# Power_Distribution_-_Spares.net
KiCad netlist of a schematic drawn in Altium Designer
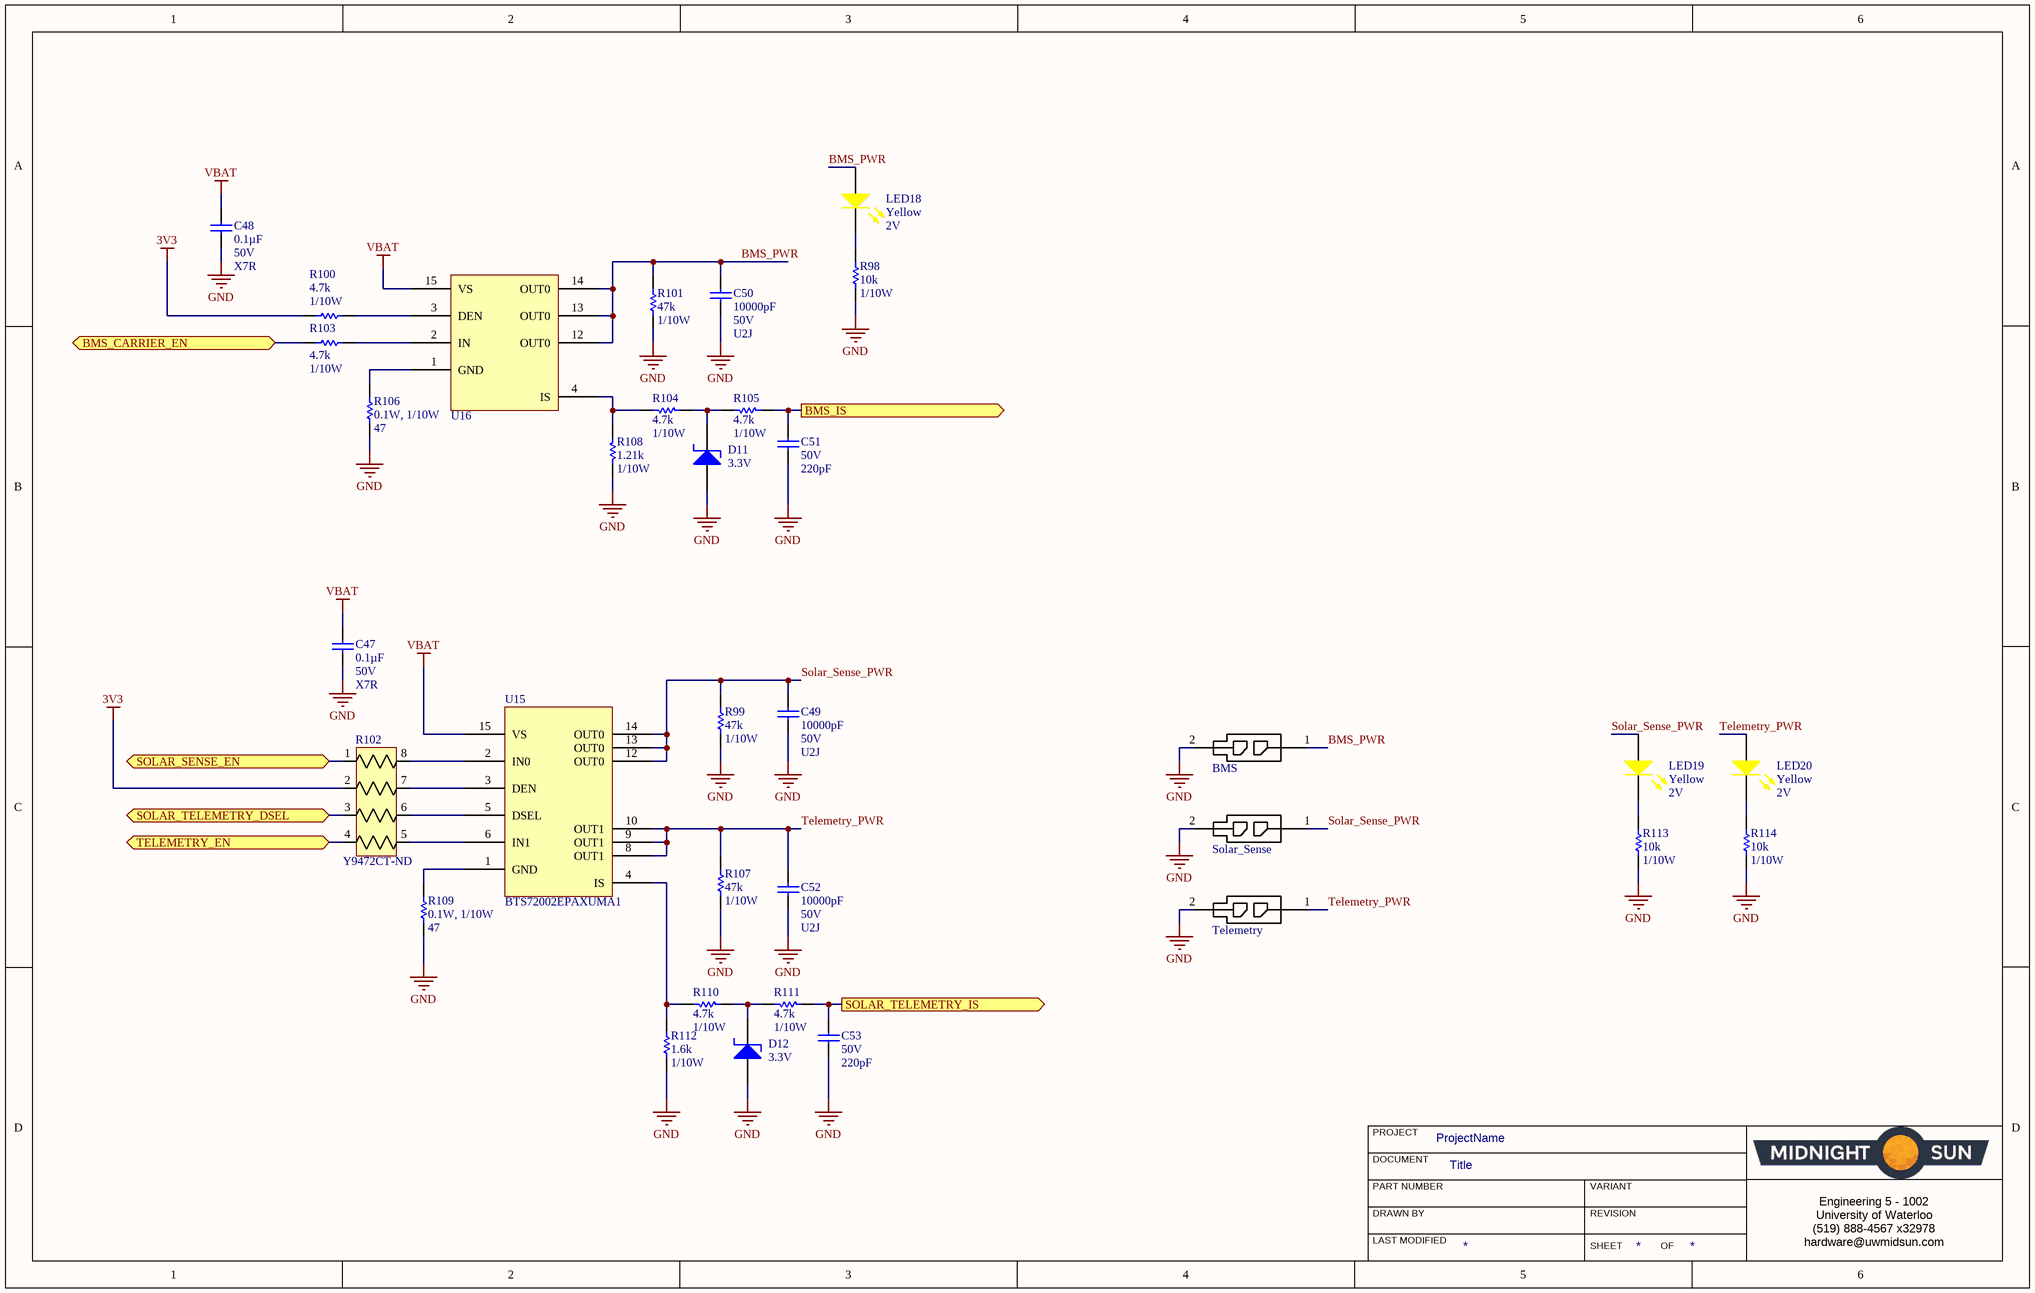
[diagram p0: Power Distribution - Spares.SchDoc]

(export (version "E")
  (design (tool "Eeschema 10.0.6"))
  (components
    (comp (ref "BMS")
      (value "CONN 2POS MICRO-FIT 3mm")
      (footprint "CONN, 2POS MICRO-FIT")
      (description "Connector Header Through Hole 2 position")
      (fields (field (name "MANUFACTURER") "Molex") (field (name "MANUFACTURER PART NUMBER") "43045-0227"))
      (libsource (lib "Schematic Diagrams") (part "CONN 2POS MICRO-FIT 3mm"))
    )
    (comp (ref "C47")
      (value "CAP CER 0.1UF 50V 10% X7R 0603")
      (footprint "CAP, 0603")
      (description "0.10µF ±10% 50V Ceramic Capacitor X7R 0603 (1608 Metric)")
      (fields
        (field (name "TOLERANCE") "±10%")
        (field (name "CAPACITANCE") "0.1µF")
        (field (name "VOLTAGE") "50V")
        (field (name "TEMPERATURE COEFFICIENT") "X7R")
      )
      (libsource (lib "Schematic Diagrams") (part "CAP CER 0.1UF 50V 10% X7R 0603"))
    )
    (comp (ref "C48")
      (value "CAP CER 0.1UF 50V 10% X7R 0603")
      (footprint "CAP, 0603")
      (description "0.10µF ±10% 50V Ceramic Capacitor X7R 0603 (1608 Metric)")
      (fields
        (field (name "TOLERANCE") "±10%")
        (field (name "CAPACITANCE") "0.1µF")
        (field (name "VOLTAGE") "50V")
        (field (name "TEMPERATURE COEFFICIENT") "X7R")
      )
      (libsource (lib "Schematic Diagrams") (part "CAP CER 0.1UF 50V 10% X7R 0603"))
    )
    (comp (ref "C49")
      (value "CAP CER 10nF 50V 5% X7R 0603")
      (footprint "CAP, 0603")
      (description "10000pF ±5% 50V Ceramic Capacitor U2J 0603 (1608 Metric)")
      (fields
        (field (name "TOLERANCE") "±5%")
        (field (name "CAPACITANCE") "10000pF")
        (field (name "VOLTAGE") "50V")
        (field (name "TEMPERATURE COEFFICIENT") "U2J")
      )
      (libsource (lib "Schematic Diagrams") (part "CAP CER 10nF 50V 5% X7R 0603"))
    )
    (comp (ref "C50")
      (value "CAP CER 10nF 50V 5% X7R 0603")
      (footprint "CAP, 0603")
      (description "10000pF ±5% 50V Ceramic Capacitor U2J 0603 (1608 Metric)")
      (fields
        (field (name "TOLERANCE") "±5%")
        (field (name "CAPACITANCE") "10000pF")
        (field (name "VOLTAGE") "50V")
        (field (name "TEMPERATURE COEFFICIENT") "U2J")
      )
      (libsource (lib "Schematic Diagrams") (part "CAP CER 10nF 50V 5% X7R 0603"))
    )
    (comp (ref "C51")
      (value "CAP CER 220PF 50V C0G/NP0 0603")
      (footprint "CAP, 0603")
      (description "220pF ±5% 50V Ceramic Capacitor C0G, NP0 0603 (1608 Metric)")
      (fields
        (field (name "MANUFACTURER") "KEMET")
        (field (name "TOLERANCE") "5%")
        (field (name "VOLTAGE RATING") "50V")
        (field (name "CAPACITANCE") "220pF")
      )
      (libsource (lib "Schematic Diagrams") (part "CAP CER 220PF 50V C0G/NP0 0603"))
    )
    (comp (ref "C52")
      (value "CAP CER 10nF 50V 5% X7R 0603")
      (footprint "CAP, 0603")
      (description "10000pF ±5% 50V Ceramic Capacitor U2J 0603 (1608 Metric)")
      (fields
        (field (name "TOLERANCE") "±5%")
        (field (name "CAPACITANCE") "10000pF")
        (field (name "VOLTAGE") "50V")
        (field (name "TEMPERATURE COEFFICIENT") "U2J")
      )
      (libsource (lib "Schematic Diagrams") (part "CAP CER 10nF 50V 5% X7R 0603"))
    )
    (comp (ref "C53")
      (value "CAP CER 220PF 50V C0G/NP0 0603")
      (footprint "CAP, 0603")
      (description "220pF ±5% 50V Ceramic Capacitor C0G, NP0 0603 (1608 Metric)")
      (fields
        (field (name "MANUFACTURER") "KEMET")
        (field (name "TOLERANCE") "5%")
        (field (name "VOLTAGE RATING") "50V")
        (field (name "CAPACITANCE") "220pF")
      )
      (libsource (lib "Schematic Diagrams") (part "CAP CER 220PF 50V C0G/NP0 0603"))
    )
    (comp (ref "D11")
      (value "DIODE ZENER 3.3V 200MW SOD323")
      (footprint "sod-323")
      (description "Zener Diode 3.3V 200mW ±5% Surface Mount SOD-323")
      (fields (field (name "VOLTAGE") "3.3V"))
      (libsource (lib "Schematic Diagrams") (part "DIODE ZENER 3.3V 200MW SOD323"))
    )
    (comp (ref "D12")
      (value "DIODE ZENER 3.3V 200MW SOD323")
      (footprint "sod-323")
      (description "Zener Diode 3.3V 200mW ±5% Surface Mount SOD-323")
      (fields (field (name "VOLTAGE") "3.3V"))
      (libsource (lib "Schematic Diagrams") (part "DIODE ZENER 3.3V 200MW SOD323"))
    )
    (comp (ref "LED18")
      (value "LED YELLOW CLEAR 2.1V 0603")
      (footprint "LED_0603")
      (description "Yellow 590nm LED Indication - Discrete 2V 0603 (1608 Metric)")
      (fields
        (field (name "MANUFACTURER") "Wurth Electronics Inc.")
        (field (name "MANUFACTURER PART NUMBER") "150060YS75000")
        (field (name "COLOR") "Yellow")
        (field (name "VOLTAGE - FORWARD (VF) (TYP)") "2V")
      )
      (libsource (lib "Schematic Diagrams") (part "LED YELLOW CLEAR 2.1V 0603"))
    )
    (comp (ref "LED19")
      (value "LED YELLOW CLEAR 2.1V 0603")
      (footprint "LED_0603")
      (description "Yellow 590nm LED Indication - Discrete 2V 0603 (1608 Metric)")
      (fields
        (field (name "MANUFACTURER") "Wurth Electronics Inc.")
        (field (name "MANUFACTURER PART NUMBER") "150060YS75000")
        (field (name "COLOR") "Yellow")
        (field (name "VOLTAGE - FORWARD (VF) (TYP)") "2V")
      )
      (libsource (lib "Schematic Diagrams") (part "LED YELLOW CLEAR 2.1V 0603"))
    )
    (comp (ref "LED20")
      (value "LED YELLOW CLEAR 2.1V 0603")
      (footprint "LED_0603")
      (description "Yellow 590nm LED Indication - Discrete 2V 0603 (1608 Metric)")
      (fields
        (field (name "MANUFACTURER") "Wurth Electronics Inc.")
        (field (name "MANUFACTURER PART NUMBER") "150060YS75000")
        (field (name "COLOR") "Yellow")
        (field (name "VOLTAGE - FORWARD (VF) (TYP)") "2V")
      )
      (libsource (lib "Schematic Diagrams") (part "LED YELLOW CLEAR 2.1V 0603"))
    )
    (comp (ref "R98")
      (value "RES 10K OHM 1% 1/10W 0603")
      (footprint "RES, 0603")
      (description "RES SMD 10K OHM 1% 1/10W 0603")
      (fields
        (field (name "TOLERANCE") "±1%")
        (field (name "RESISTANCE") "10k")
        (field (name "POWER") "1/10W")
      )
      (libsource (lib "Schematic Diagrams") (part "RES 10K OHM 1% 1/10W 0603"))
    )
    (comp (ref "R99")
      (value "RES 47K OHM 1% 1/10W 0603")
      (footprint "RES, 0603")
      (description "47 kOhms ±1% 0.1W, 1/10W Chip Resistor 0603 (1608 Metric) Automotive AEC-Q200 Thick Film")
      (fields
        (field (name "MANUFACTURER") "Panasonic")
        (field (name "MANUFACTURER PART NUMBER") "ERJ3EKF4702V")
        (field (name "RESISTANCE") "47k")
        (field (name "POWER RATING") "1/10W")
      )
      (libsource (lib "Schematic Diagrams") (part "RES 47K OHM 1% 1/10W 0603"))
    )
    (comp (ref "R100")
      (value "RES 4.7K OHM 1% 1/10W 0603")
      (footprint "RES, 0603")
      (description "4.7k Ohm ±1% 0.1W, 1/10W Chip Resistor 0603 (1608 Metric) Moisture Resistant Thick Film")
      (fields
        (field (name "TOLERANCE") "±1%")
        (field (name "RESISTANCE (OHMS)") "4.7k")
        (field (name "POWER (WATTS)") "1/10W")
      )
      (libsource (lib "Schematic Diagrams") (part "RES 4.7K OHM 1% 1/10W 0603"))
    )
    (comp (ref "R101")
      (value "RES 47K OHM 1% 1/10W 0603")
      (footprint "RES, 0603")
      (description "47 kOhms ±1% 0.1W, 1/10W Chip Resistor 0603 (1608 Metric) Automotive AEC-Q200 Thick Film")
      (fields
        (field (name "MANUFACTURER") "Panasonic")
        (field (name "MANUFACTURER PART NUMBER") "ERJ3EKF4702V")
        (field (name "RESISTANCE") "47k")
        (field (name "POWER RATING") "1/10W")
      )
      (libsource (lib "Schematic Diagrams") (part "RES 47K OHM 1% 1/10W 0603"))
    )
    (comp (ref "R102")
      (value "RES ARRAY 4 RES 4.7K OHM 1206")
      (footprint "RES ARRAY 4RES 1206")
      (fields (field (name "TOLERANCE") "±5%") (field (name "SUPPLIER PART NUMBER 1") "Y9472CT-ND"))
      (libsource (lib "Schematic Diagrams") (part "RES ARRAY 4 RES 4.7K OHM 1206"))
    )
    (comp (ref "R103")
      (value "RES 4.7K OHM 1% 1/10W 0603")
      (footprint "RES, 0603")
      (description "4.7k Ohm ±1% 0.1W, 1/10W Chip Resistor 0603 (1608 Metric) Moisture Resistant Thick Film")
      (fields
        (field (name "TOLERANCE") "±1%")
        (field (name "RESISTANCE (OHMS)") "4.7k")
        (field (name "POWER (WATTS)") "1/10W")
      )
      (libsource (lib "Schematic Diagrams") (part "RES 4.7K OHM 1% 1/10W 0603"))
    )
    (comp (ref "R104")
      (value "RES 4.7K OHM 1% 1/10W 0603")
      (footprint "RES, 0603")
      (description "4.7k Ohm ±1% 0.1W, 1/10W Chip Resistor 0603 (1608 Metric) Moisture Resistant Thick Film")
      (fields
        (field (name "TOLERANCE") "±1%")
        (field (name "RESISTANCE (OHMS)") "4.7k")
        (field (name "POWER (WATTS)") "1/10W")
      )
      (libsource (lib "Schematic Diagrams") (part "RES 4.7K OHM 1% 1/10W 0603"))
    )
    (comp (ref "R105")
      (value "RES 4.7K OHM 1% 1/10W 0603")
      (footprint "RES, 0603")
      (description "4.7k Ohm ±1% 0.1W, 1/10W Chip Resistor 0603 (1608 Metric) Moisture Resistant Thick Film")
      (fields
        (field (name "TOLERANCE") "±1%")
        (field (name "RESISTANCE (OHMS)") "4.7k")
        (field (name "POWER (WATTS)") "1/10W")
      )
      (libsource (lib "Schematic Diagrams") (part "RES 4.7K OHM 1% 1/10W 0603"))
    )
    (comp (ref "R106")
      (value "RES SMD 47 OHM 1% 1/10W 0603")
      (footprint "RES, 0603")
      (fields
        (field (name "TOLERANCE") "±1%")
        (field (name "POWER (WATTS)") "0.1W, 1/10W")
        (field (name "VALUES") "47")
      )
      (libsource (lib "Schematic Diagrams") (part "RES SMD 47 OHM 1% 1/10W 0603"))
    )
    (comp (ref "R107")
      (value "RES 47K OHM 1% 1/10W 0603")
      (footprint "RES, 0603")
      (description "47 kOhms ±1% 0.1W, 1/10W Chip Resistor 0603 (1608 Metric) Automotive AEC-Q200 Thick Film")
      (fields
        (field (name "MANUFACTURER") "Panasonic")
        (field (name "MANUFACTURER PART NUMBER") "ERJ3EKF4702V")
        (field (name "RESISTANCE") "47k")
        (field (name "POWER RATING") "1/10W")
      )
      (libsource (lib "Schematic Diagrams") (part "RES 47K OHM 1% 1/10W 0603"))
    )
    (comp (ref "R108")
      (value "RES 1.21K OHM 1% 1/10W 0603")
      (footprint "RES, 0603")
      (description "1.21k Ohm ±1% 0.1W, 1/10W Chip Resistor 0603 (1608 Metric) Moisture Resistant Thick Film")
      (fields
        (field (name "TOLERANCE") "±1%")
        (field (name "RESISTANCE") "1.21k")
        (field (name "POWER") "1/10W")
      )
      (libsource (lib "Schematic Diagrams") (part "RES 1.21K OHM 1% 1/10W 0603"))
    )
    (comp (ref "R109")
      (value "RES SMD 47 OHM 1% 1/10W 0603")
      (footprint "RES, 0603")
      (fields
        (field (name "TOLERANCE") "±1%")
        (field (name "POWER (WATTS)") "0.1W, 1/10W")
        (field (name "VALUES") "47")
      )
      (libsource (lib "Schematic Diagrams") (part "RES SMD 47 OHM 1% 1/10W 0603"))
    )
    (comp (ref "R110")
      (value "RES 4.7K OHM 1% 1/10W 0603")
      (footprint "RES, 0603")
      (description "4.7k Ohm ±1% 0.1W, 1/10W Chip Resistor 0603 (1608 Metric) Moisture Resistant Thick Film")
      (fields
        (field (name "TOLERANCE") "±1%")
        (field (name "RESISTANCE (OHMS)") "4.7k")
        (field (name "POWER (WATTS)") "1/10W")
      )
      (libsource (lib "Schematic Diagrams") (part "RES 4.7K OHM 1% 1/10W 0603"))
    )
    (comp (ref "R111")
      (value "RES 4.7K OHM 1% 1/10W 0603")
      (footprint "RES, 0603")
      (description "4.7k Ohm ±1% 0.1W, 1/10W Chip Resistor 0603 (1608 Metric) Moisture Resistant Thick Film")
      (fields
        (field (name "TOLERANCE") "±1%")
        (field (name "RESISTANCE (OHMS)") "4.7k")
        (field (name "POWER (WATTS)") "1/10W")
      )
      (libsource (lib "Schematic Diagrams") (part "RES 4.7K OHM 1% 1/10W 0603"))
    )
    (comp (ref "R112")
      (value "RES 1.6K OHM 1% 1/10W 0603")
      (footprint "RES, 0603")
      (description "1.6 kOhms ±1% 0.1W, 1/10W Chip Resistor 0603 (1608 Metric) Moisture Resistant Thick Film")
      (fields
        (field (name "MANUFACTURER") "Yageo")
        (field (name "MANUFACTURER PART NUMBER") "RC0603FR-071K6L")
        (field (name "RESISTANCE") "1.6k")
        (field (name "POWER RATING") "1/10W")
      )
      (libsource (lib "Schematic Diagrams") (part "RES 1.6K OHM 1% 1/10W 0603"))
    )
    (comp (ref "R113")
      (value "RES 10K OHM 1% 1/10W 0603")
      (footprint "RES, 0603")
      (description "RES SMD 10K OHM 1% 1/10W 0603")
      (fields
        (field (name "TOLERANCE") "±1%")
        (field (name "RESISTANCE") "10k")
        (field (name "POWER") "1/10W")
      )
      (libsource (lib "Schematic Diagrams") (part "RES 10K OHM 1% 1/10W 0603"))
    )
    (comp (ref "R114")
      (value "RES 10K OHM 1% 1/10W 0603")
      (footprint "RES, 0603")
      (description "RES SMD 10K OHM 1% 1/10W 0603")
      (fields
        (field (name "TOLERANCE") "±1%")
        (field (name "RESISTANCE") "10k")
        (field (name "POWER") "1/10W")
      )
      (libsource (lib "Schematic Diagrams") (part "RES 10K OHM 1% 1/10W 0603"))
    )
    (comp (ref "Solar_Sense")
      (value "CONN 2POS MICRO-FIT 3mm")
      (footprint "CONN, 2POS MICRO-FIT")
      (description "Connector Header Through Hole 2 position")
      (fields (field (name "MANUFACTURER") "Molex") (field (name "MANUFACTURER PART NUMBER") "43045-0227"))
      (libsource (lib "Schematic Diagrams") (part "CONN 2POS MICRO-FIT 3mm"))
    )
    (comp (ref "Telemetry")
      (value "CONN 2POS MICRO-FIT 3mm")
      (footprint "CONN, 2POS MICRO-FIT")
      (description "Connector Header Through Hole 2 position")
      (fields (field (name "MANUFACTURER") "Molex") (field (name "MANUFACTURER PART NUMBER") "43045-0227"))
      (libsource (lib "Schematic Diagrams") (part "CONN 2POS MICRO-FIT 3mm"))
    )
    (comp (ref "U15")
      (value "IC LOAD SWITCH BTS7200-2EPA PG-TSDSO-14_1")
      (footprint "IC LOAD SWITCH PG-TSDSO-14-22")
      (description "Power Switch/Driver 1:1 N-Channel 1.2A PG-TSDSO-14-22")
      (fields
        (field (name "MANUFACTURER") "Infineon")
        (field (name "MANUFACTURER PART NUMBER") "BTS72002EPAXUMA1")
      )
      (libsource (lib "Schematic Diagrams") (part "IC LOAD SWITCH BTS7200-2EPA PG-TSDSO-14_1"))
    )
    (comp (ref "U16")
      (value "IC LOAD SWITCH BTS70401EPA PG-TSDSO-14-22")
      (footprint "IC LOAD SWITCH PG-TSDSO-14-22")
      (description "Power Switch/Driver 1:1 N-Channel 4.5A PG-TSDSO-14-22")
      (fields
        (field (name "MANUFACTURER") "Infineon")
        (field (name "MANUFACTURER PART NUMBER") "BTS70401EPAXUMA1")
      )
      (libsource (lib "Schematic Diagrams") (part "IC LOAD SWITCH BTS70401EPA PG-TSDSO-14-22"))
    )
  )
  (nets
    (net (code "1") (name "/BMS_CARRIER_EN") (class "Default")
      (node (ref "R103") (pin "1") (pinfunction "1_1") (pintype "passive"))
    )
    (net (code "2") (name "/BMS_IS") (class "Default")
      (node (ref "C51") (pin "1") (pinfunction "1_1") (pintype "passive"))
      (node (ref "R105") (pin "1") (pinfunction "1_1") (pintype "passive"))
    )
    (net (code "3") (name "/BMS_PWR") (class "Default")
      (node (ref "BMS") (pin "1") (pinfunction "1_1") (pintype "passive"))
      (node (ref "C50") (pin "1") (pinfunction "1_1") (pintype "passive"))
      (node (ref "LED18") (pin "1") (pinfunction "A_1") (pintype "passive"))
      (node (ref "R101") (pin "1") (pinfunction "1_1") (pintype "passive"))
      (node (ref "U16") (pin "12") (pinfunction "OUT0_12") (pintype "passive"))
      (node (ref "U16") (pin "13") (pinfunction "OUT0_13") (pintype "passive"))
      (node (ref "U16") (pin "14") (pinfunction "OUT0_14") (pintype "passive"))
    )
    (net (code "4") (name "/SOLAR_SENSE_EN") (class "Default")
      (node (ref "R102") (pin "1") (pinfunction "1_1") (pintype "passive"))
    )
    (net (code "5") (name "/SOLAR_TELEMETRY_DSEL") (class "Default")
      (node (ref "R102") (pin "3") (pinfunction "3_3") (pintype "passive"))
    )
    (net (code "6") (name "/SOLAR_TELEMETRY_IS") (class "Default")
      (node (ref "C53") (pin "1") (pinfunction "1_1") (pintype "passive"))
      (node (ref "R111") (pin "1") (pinfunction "1_1") (pintype "passive"))
    )
    (net (code "7") (name "/Solar_Sense_PWR") (class "Default")
      (node (ref "C49") (pin "1") (pinfunction "1_1") (pintype "passive"))
      (node (ref "LED19") (pin "1") (pinfunction "A_1") (pintype "passive"))
      (node (ref "R99") (pin "1") (pinfunction "1_1") (pintype "passive"))
      (node (ref "Solar_Sense") (pin "1") (pinfunction "1_1") (pintype "passive"))
      (node (ref "U15") (pin "12") (pinfunction "OUT0_12") (pintype "passive"))
      (node (ref "U15") (pin "13") (pinfunction "OUT0_13") (pintype "passive"))
      (node (ref "U15") (pin "14") (pinfunction "OUT0_14") (pintype "passive"))
    )
    (net (code "8") (name "/TELEMETRY_EN") (class "Default")
      (node (ref "R102") (pin "4") (pinfunction "4_4") (pintype "passive"))
    )
    (net (code "9") (name "/Telemetry_PWR") (class "Default")
      (node (ref "C52") (pin "1") (pinfunction "1_1") (pintype "passive"))
      (node (ref "LED20") (pin "1") (pinfunction "A_1") (pintype "passive"))
      (node (ref "R107") (pin "1") (pinfunction "1_1") (pintype "passive"))
      (node (ref "Telemetry") (pin "1") (pinfunction "1_1") (pintype "passive"))
      (node (ref "U15") (pin "10") (pinfunction "OUT1_10") (pintype "passive"))
      (node (ref "U15") (pin "8") (pinfunction "OUT1_8") (pintype "passive"))
      (node (ref "U15") (pin "9") (pinfunction "OUT1_9") (pintype "passive"))
    )
    (net (code "10") (name "3V3") (class "Default")
      (node (ref "R100") (pin "1") (pinfunction "1_1") (pintype "passive"))
      (node (ref "R102") (pin "2") (pinfunction "2_2") (pintype "passive"))
    )
    (net (code "11") (name "GND") (class "Default")
      (node (ref "BMS") (pin "2") (pinfunction "2_2") (pintype "passive"))
      (node (ref "C47") (pin "2") (pinfunction "2_2") (pintype "passive"))
      (node (ref "C48") (pin "2") (pinfunction "2_2") (pintype "passive"))
      (node (ref "C49") (pin "2") (pinfunction "2_2") (pintype "passive"))
      (node (ref "C50") (pin "2") (pinfunction "2_2") (pintype "passive"))
      (node (ref "C51") (pin "2") (pinfunction "2_2") (pintype "passive"))
      (node (ref "C52") (pin "2") (pinfunction "2_2") (pintype "passive"))
      (node (ref "C53") (pin "2") (pinfunction "2_2") (pintype "passive"))
      (node (ref "D11") (pin "1") (pinfunction "A_1") (pintype "passive"))
      (node (ref "D12") (pin "1") (pinfunction "A_1") (pintype "passive"))
      (node (ref "R101") (pin "2") (pinfunction "2_2") (pintype "passive"))
      (node (ref "R106") (pin "2") (pinfunction "2_2") (pintype "passive"))
      (node (ref "R107") (pin "2") (pinfunction "2_2") (pintype "passive"))
      (node (ref "R108") (pin "2") (pinfunction "2_2") (pintype "passive"))
      (node (ref "R109") (pin "2") (pinfunction "2_2") (pintype "passive"))
      (node (ref "R112") (pin "2") (pinfunction "2_2") (pintype "passive"))
      (node (ref "R113") (pin "2") (pinfunction "2_2") (pintype "passive"))
      (node (ref "R114") (pin "2") (pinfunction "2_2") (pintype "passive"))
      (node (ref "R98") (pin "2") (pinfunction "2_2") (pintype "passive"))
      (node (ref "R99") (pin "2") (pinfunction "2_2") (pintype "passive"))
      (node (ref "Solar_Sense") (pin "2") (pinfunction "2_2") (pintype "passive"))
      (node (ref "Telemetry") (pin "2") (pinfunction "2_2") (pintype "passive"))
    )
    (net (code "12") (name "Net-(D11-K)") (class "Default")
      (node (ref "D11") (pin "2") (pinfunction "K_2") (pintype "passive"))
      (node (ref "R104") (pin "1") (pinfunction "1_1") (pintype "passive"))
      (node (ref "R105") (pin "2") (pinfunction "2_2") (pintype "passive"))
    )
    (net (code "13") (name "Net-(D12-K)") (class "Default")
      (node (ref "D12") (pin "2") (pinfunction "K_2") (pintype "passive"))
      (node (ref "R110") (pin "1") (pinfunction "1_1") (pintype "passive"))
      (node (ref "R111") (pin "2") (pinfunction "2_2") (pintype "passive"))
    )
    (net (code "14") (name "Net-(LED18-K)") (class "Default")
      (node (ref "LED18") (pin "2") (pinfunction "K_2") (pintype "passive"))
      (node (ref "R98") (pin "1") (pinfunction "1_1") (pintype "passive"))
    )
    (net (code "15") (name "Net-(LED19-K)") (class "Default")
      (node (ref "LED19") (pin "2") (pinfunction "K_2") (pintype "passive"))
      (node (ref "R113") (pin "1") (pinfunction "1_1") (pintype "passive"))
    )
    (net (code "16") (name "Net-(LED20-K)") (class "Default")
      (node (ref "LED20") (pin "2") (pinfunction "K_2") (pintype "passive"))
      (node (ref "R114") (pin "1") (pinfunction "1_1") (pintype "passive"))
    )
    (net (code "17") (name "Net-(U15-DEN)") (class "Default")
      (node (ref "R102") (pin "7") (pinfunction "7_7") (pintype "passive"))
      (node (ref "U15") (pin "3") (pinfunction "DEN_3") (pintype "passive"))
    )
    (net (code "18") (name "Net-(U15-DSEL)") (class "Default")
      (node (ref "R102") (pin "6") (pinfunction "6_6") (pintype "passive"))
      (node (ref "U15") (pin "5") (pinfunction "DSEL_5") (pintype "passive"))
    )
    (net (code "19") (name "Net-(U15-GND)") (class "Default")
      (node (ref "R109") (pin "1") (pinfunction "1_1") (pintype "passive"))
      (node (ref "U15") (pin "1") (pinfunction "GND_1") (pintype "passive"))
    )
    (net (code "20") (name "Net-(U15-IN0)") (class "Default")
      (node (ref "R102") (pin "8") (pinfunction "8_8") (pintype "passive"))
      (node (ref "U15") (pin "2") (pinfunction "IN0_2") (pintype "passive"))
    )
    (net (code "21") (name "Net-(U15-IN1)") (class "Default")
      (node (ref "R102") (pin "5") (pinfunction "5_5") (pintype "passive"))
      (node (ref "U15") (pin "6") (pinfunction "IN1_6") (pintype "passive"))
    )
    (net (code "22") (name "Net-(U15-IS)") (class "Default")
      (node (ref "R110") (pin "2") (pinfunction "2_2") (pintype "passive"))
      (node (ref "R112") (pin "1") (pinfunction "1_1") (pintype "passive"))
      (node (ref "U15") (pin "4") (pinfunction "IS_4") (pintype "passive"))
    )
    (net (code "23") (name "Net-(U16-DEN)") (class "Default")
      (node (ref "R100") (pin "2") (pinfunction "2_2") (pintype "passive"))
      (node (ref "U16") (pin "3") (pinfunction "DEN_3") (pintype "passive"))
    )
    (net (code "24") (name "Net-(U16-GND)") (class "Default")
      (node (ref "R106") (pin "1") (pinfunction "1_1") (pintype "passive"))
      (node (ref "U16") (pin "1") (pinfunction "GND_1") (pintype "passive"))
    )
    (net (code "25") (name "Net-(U16-IN)") (class "Default")
      (node (ref "R103") (pin "2") (pinfunction "2_2") (pintype "passive"))
      (node (ref "U16") (pin "2") (pinfunction "IN_2") (pintype "passive"))
    )
    (net (code "26") (name "Net-(U16-IS)") (class "Default")
      (node (ref "R104") (pin "2") (pinfunction "2_2") (pintype "passive"))
      (node (ref "R108") (pin "1") (pinfunction "1_1") (pintype "passive"))
      (node (ref "U16") (pin "4") (pinfunction "IS_4") (pintype "passive"))
    )
    (net (code "27") (name "VBAT") (class "Default")
      (node (ref "C47") (pin "1") (pinfunction "1_1") (pintype "passive"))
      (node (ref "C48") (pin "1") (pinfunction "1_1") (pintype "passive"))
      (node (ref "U15") (pin "15") (pinfunction "VS_15") (pintype "passive"))
      (node (ref "U16") (pin "15") (pinfunction "VS_15") (pintype "passive"))
    )
  )
)
